# Underwater_vehicle-V2_0.net
KiCad netlist of a schematic drawn in Altium Designer
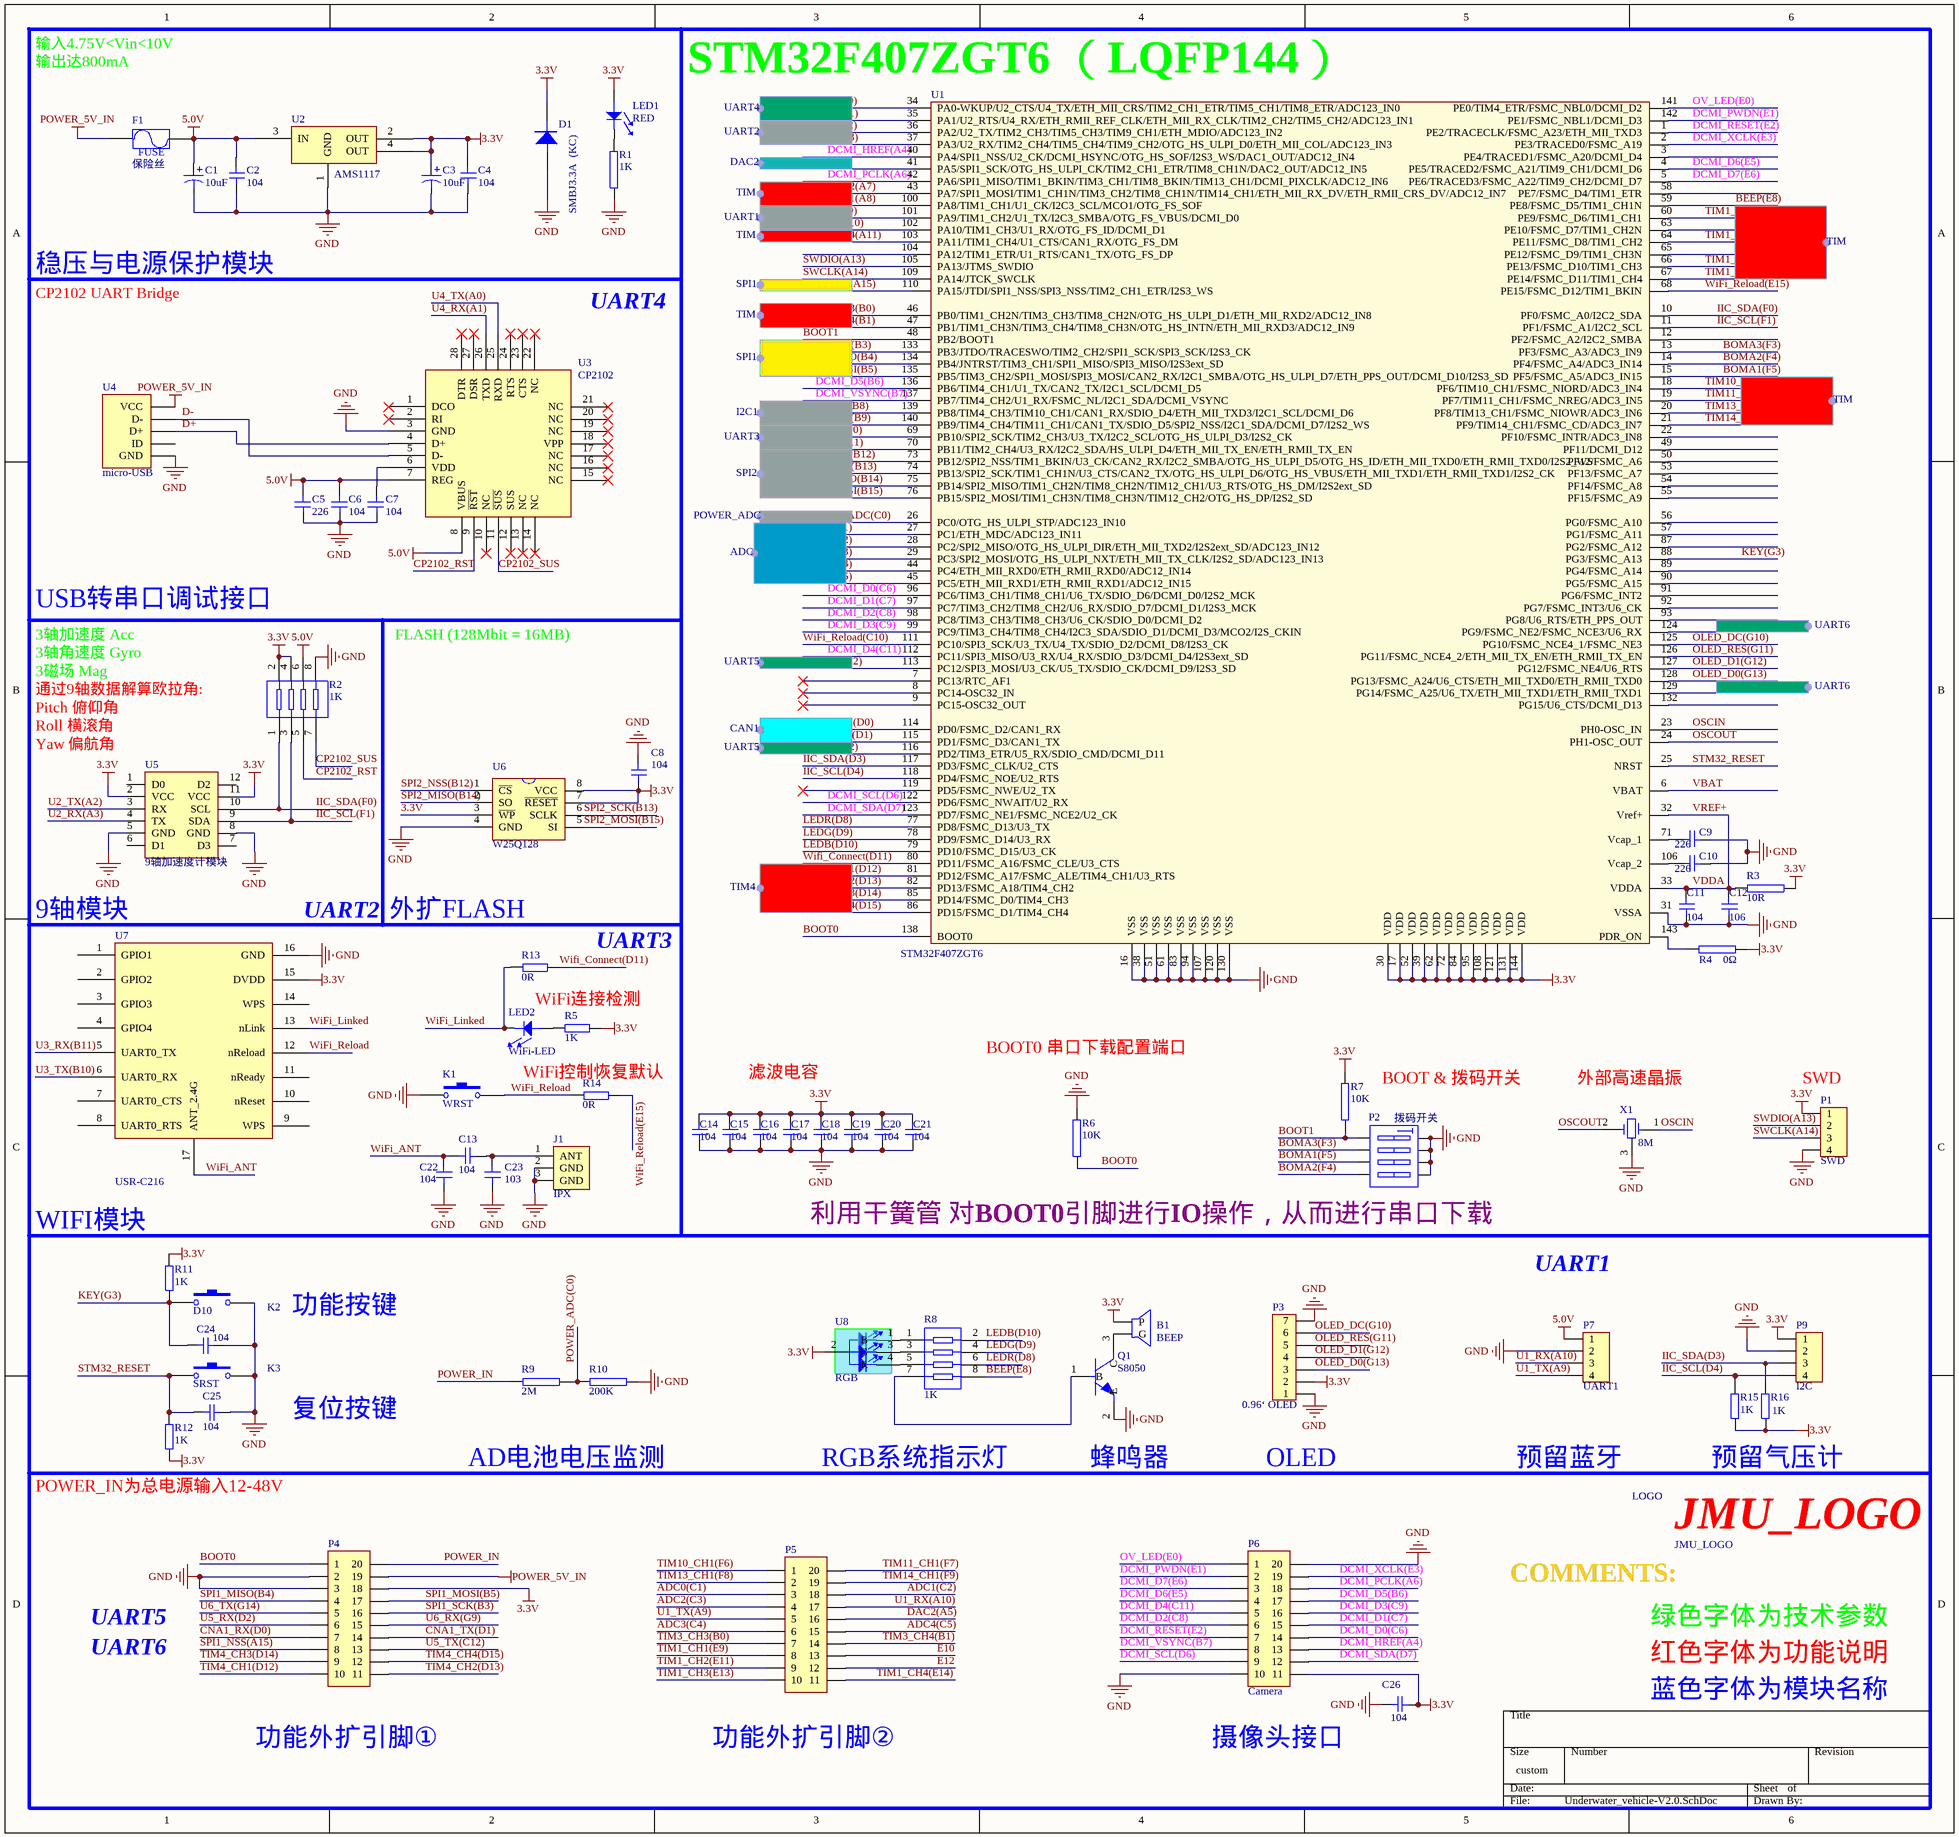
[diagram p0: Underwater_vehicle-V2.0.SchDoc]

(export (version "E")
  (design (tool "Eeschema 10.0.6"))
  (components
    (comp (ref "B1") (value "BEEP") (footprint "BUZZER") (libsource (lib "EXPLORER") (part "BEEP")))
    (comp (ref "C1")
      (value "10uF")
      (footprint "TAJ-A")
      (description "极性贴片电容")
      (libsource (lib "集大电协1.1.0") (part "Pol Cap"))
    )
    (comp (ref "C2")
      (value "104")
      (footprint "0805C")
      (description "无极贴片电容")
      (libsource (lib "集大电协1.1.0") (part "Cap1"))
    )
    (comp (ref "C3")
      (value "10uF")
      (footprint "TAJ-A")
      (description "极性贴片电容")
      (libsource (lib "集大电协1.1.0") (part "Pol Cap"))
    )
    (comp (ref "C4")
      (value "104")
      (footprint "0805C")
      (description "无极贴片电容")
      (libsource (lib "集大电协1.1.0") (part "Cap1"))
    )
    (comp (ref "C5")
      (value "226")
      (footprint "0805C")
      (description "无极贴片电容")
      (libsource (lib "集大电协1.1.0") (part "Cap1"))
    )
    (comp (ref "C6")
      (value "104")
      (footprint "0805C")
      (description "无极贴片电容")
      (libsource (lib "集大电协1.1.0") (part "Cap1"))
    )
    (comp (ref "C7")
      (value "104")
      (footprint "0805C")
      (description "无极贴片电容")
      (libsource (lib "集大电协1.1.0") (part "Cap1"))
    )
    (comp (ref "C8")
      (value "104")
      (footprint "0805C")
      (description "无极贴片电容")
      (libsource (lib "集大电协1.1.0") (part "Cap1"))
    )
    (comp (ref "C9") (value "226") (footprint "0805C") (libsource (lib "窝牛器件封装") (part "C1")))
    (comp (ref "C10") (value "226") (footprint "0805C") (libsource (lib "窝牛器件封装") (part "C1")))
    (comp (ref "C11") (value "104") (footprint "0805C") (libsource (lib "窝牛器件封装") (part "C1")))
    (comp (ref "C12") (value "106") (footprint "0805C") (libsource (lib "窝牛器件封装") (part "C1")))
    (comp (ref "C13")
      (value "104")
      (footprint "0805C")
      (description "无极贴片电容")
      (libsource (lib "集大电协1.1.2") (part "Cap1"))
    )
    (comp (ref "C14") (value "104") (footprint "0805C") (libsource (lib "窝牛器件封装") (part "C1")))
    (comp (ref "C15") (value "104") (footprint "0805C") (libsource (lib "窝牛器件封装") (part "C1")))
    (comp (ref "C16") (value "104") (footprint "0805C") (libsource (lib "窝牛器件封装") (part "C1")))
    (comp (ref "C17") (value "104") (footprint "0805C") (libsource (lib "窝牛器件封装") (part "C1")))
    (comp (ref "C18") (value "104") (footprint "0805C") (libsource (lib "窝牛器件封装") (part "C1")))
    (comp (ref "C19") (value "104") (footprint "0805C") (libsource (lib "窝牛器件封装") (part "C1")))
    (comp (ref "C20") (value "104") (footprint "0805C") (libsource (lib "窝牛器件封装") (part "C1")))
    (comp (ref "C21") (value "104") (footprint "0805C") (libsource (lib "窝牛器件封装") (part "C1")))
    (comp (ref "C22")
      (value "104")
      (footprint "0805C")
      (description "无极贴片电容")
      (libsource (lib "集大电协1.1.2") (part "Cap1"))
    )
    (comp (ref "C23")
      (value "103")
      (footprint "0805C")
      (description "无极贴片电容")
      (libsource (lib "集大电协1.1.2") (part "Cap1"))
    )
    (comp (ref "C24") (value "104") (footprint "0805C") (libsource (lib "窝牛器件封装") (part "C1")))
    (comp (ref "C25") (value "104") (footprint "0805C") (libsource (lib "窝牛器件封装") (part "C1")))
    (comp (ref "C26")
      (value "104")
      (footprint "0805C")
      (description "无极贴片电容")
      (libsource (lib "集大电协1.1.5") (part "Cap1"))
    )
    (comp (ref "D1")
      (value "SMBJ3.3A  (KC)")
      (footprint "SMBJ")
      (description "二极管")
      (libsource (lib "集大电协1.1.0") (part "Diode"))
    )
    (comp (ref "F1") (value "保险丝") (footprint "1812") (libsource (lib "集大电协1.1.2") (part "Fuse")))
    (comp (ref "J1") (value "IPX") (footprint "IPX天线底座") (libsource (lib "集大电协1.1.2") (part "IPX天线座")))
    (comp (ref "K1")
      (value "WRST")
      (footprint "贴片按键")
      (description "轻触开关")
      (libsource (lib "集大电协1.1.2") (part "轻触按键"))
    )
    (comp (ref "K2") (value "D10") (footprint "贴片按键") (libsource (lib "窝牛器件封装") (part "Key(两脚贴片)")))
    (comp (ref "K3") (value "SRST") (footprint "贴片按键") (libsource (lib "窝牛器件封装") (part "Key(两脚贴片)")))
    (comp (ref "LED1")
      (value "RED")
      (footprint "0805LED(RED)")
      (description "发光二极管")
      (libsource (lib "集大电协1.1.2") (part "LED"))
    )
    (comp (ref "LED2")
      (value "WiFi-LED")
      (footprint "0805LED(GREEN)")
      (description "发光二极管")
      (libsource (lib "集大电协1.1.2") (part "LED"))
    )
    (comp (ref "LOGO")
      (value "JMU_LOGO")
      (footprint "JMU_LOGO(1.35cm)")
      (description "LOGO")
      (libsource (lib "集大电协1.1.5") (part "JMU_LOGO"))
    )
    (comp (ref "P1")
      (value "SWD")
      (footprint "Header 4")
      (description "排针")
      (libsource (lib "集大电协1.1.0") (part "Header 4"))
    )
    (comp (ref "P2")
      (value "拨码开关")
      (footprint "拨码开关(4位贴片)")
      (description "4位拨码开关")
      (libsource (lib "集大电协1.1.2") (part "拨码开关4"))
    )
    (comp (ref "P3")
      (value "0.96‘ OLED")
      (footprint "Header 7")
      (description "排针")
      (libsource (lib "集大电协1.1.5") (part "Header 7"))
    )
    (comp (ref "P4") (value "~") (footprint "Header 10X2") (libsource (lib "集大电协1.1.2") (part "Header 10X2")))
    (comp (ref "P5") (value "~") (footprint "Header 10X2") (libsource (lib "集大电协1.1.2") (part "Header 10X2")))
    (comp (ref "P6")
      (value "Camera")
      (footprint "Header 10X2")
      (libsource (lib "集大电协1.1.2") (part "Header 10X2"))
    )
    (comp (ref "P7")
      (value "UART1")
      (footprint "Header 4(排母)")
      (description "排针")
      (libsource (lib "集大电协1.1.5") (part "Header 4"))
    )
    (comp (ref "P9")
      (value "I2C")
      (footprint "Header 4(排母)")
      (description "排针")
      (libsource (lib "集大电协1.1.5") (part "Header 4"))
    )
    (comp (ref "Q1")
      (value "S8050")
      (footprint "SOT-23")
      (description "NPN三极管")
      (libsource (lib "集大电协1.1.2") (part "NPN"))
    )
    (comp (ref "R1") (value "1K") (footprint "0805R") (libsource (lib "窝牛器件封装") (part "R1")))
    (comp (ref "R2")
      (value "1K")
      (footprint "排阻(4位贴片)")
      (description "排阻")
      (libsource (lib "集大电协1.1.2") (part "Res-4"))
    )
    (comp (ref "R3") (value "10R") (footprint "0805R") (libsource (lib "窝牛器件封装") (part "R1")))
    (comp (ref "R4") (value "0Ω") (footprint "0805R") (libsource (lib "窝牛器件封装") (part "R1")))
    (comp (ref "R5")
      (value "1K")
      (footprint "0805R")
      (description "电阻")
      (libsource (lib "集大电协1.1.2") (part "Res"))
    )
    (comp (ref "R6") (value "10K") (footprint "0805R") (libsource (lib "窝牛器件封装") (part "R1")))
    (comp (ref "R7") (value "10K") (footprint "0805R") (libsource (lib "窝牛器件封装") (part "R1")))
    (comp (ref "R8")
      (value "1K")
      (footprint "排阻(4位贴片)")
      (description "排阻")
      (libsource (lib "集大电协1.1.2") (part "Res-4"))
    )
    (comp (ref "R9") (value "2M") (footprint "0805R") (libsource (lib "窝牛器件封装") (part "R1")))
    (comp (ref "R10") (value "200K") (footprint "0805R") (libsource (lib "窝牛器件封装") (part "R1")))
    (comp (ref "R11")
      (value "1K")
      (footprint "0805R")
      (description "电阻")
      (libsource (lib "集大电协1.1.5") (part "Res"))
    )
    (comp (ref "R12")
      (value "1K")
      (footprint "0805R")
      (description "电阻")
      (libsource (lib "集大电协1.1.5") (part "Res"))
    )
    (comp (ref "R13")
      (value "0R")
      (footprint "0805R")
      (description "电阻")
      (libsource (lib "集大电协1.1.5") (part "Res"))
    )
    (comp (ref "R14")
      (value "0R")
      (footprint "0805R")
      (description "电阻")
      (libsource (lib "集大电协1.1.5") (part "Res"))
    )
    (comp (ref "R15")
      (value "1K")
      (footprint "0805R")
      (description "电阻")
      (libsource (lib "集大电协1.2") (part "Res"))
    )
    (comp (ref "R16")
      (value "1K")
      (footprint "0805R")
      (description "电阻")
      (libsource (lib "集大电协1.2") (part "Res"))
    )
    (comp (ref "U1")
      (value "STM32F407ZGT6")
      (footprint "LQFP-144")
      (libsource (lib "窝牛器件封装") (part "STM32F407ZET6"))
    )
    (comp (ref "U2")
      (value "AMS1117")
      (footprint "SOT-223")
      (description "电源芯片")
      (libsource (lib "集大电协1.1.0") (part "AMS1117-3.3V/5.0V"))
    )
    (comp (ref "U3")
      (value "CP2102")
      (footprint "QFN-28")
      (description "USB转串口芯片")
      (libsource (lib "集大电协1.1.0") (part "CP2102"))
    )
    (comp (ref "U4")
      (value "micro-USB")
      (footprint "Micro-USB (兼容牛角)")
      (description "USB接口")
      (libsource (lib "集大电协1.1.2") (part "micro-USB"))
    )
    (comp (ref "U5") (value "9轴加速度计模块") (footprint "9轴加速度计") (libsource (lib "窝牛器件封装") (part "9轴加速度计")))
    (comp (ref "U6")
      (value "W25Q128")
      (footprint "SOW-8")
      (description "FLASH芯片")
      (libsource (lib "集大电协1.1.0") (part "W25Q128"))
    )
    (comp (ref "U7") (value "USR-C216") (footprint "USR-C216") (libsource (lib "集大电协1.2") (part "USR-C216")))
    (comp (ref "U8") (value "RGB") (footprint "RGB-3528") (libsource (lib "集大电协1.1.2") (part "RGB")))
    (comp (ref "X1") (value "8M") (footprint "三脚贴片8M晶振") (libsource (lib "集大电协1.1.2") (part "XTAL三脚贴片晶振")))
  )
  (nets
    (net (code "2") (name "/ADC0(C1)") (class "Default")
      (node (ref "P5") (pin "3") (pinfunction "3_3") (pintype "passive"))
      (node (ref "U1") (pin "27") (pinfunction "PC1/ETH_MDC/ADC123_IN11_27") (pintype "passive"))
    )
    (net (code "3") (name "/ADC1(C2)") (class "Default")
      (node (ref "P5") (pin "18") (pinfunction "18_18") (pintype "passive"))
      (node (ref "U1") (pin "28") (pinfunction "PC2/SPI2_MISO/OTG_HS_ULPI_DIR/ETH_MII_TXD2/I2S2ext_SD/ADC123_IN12_28") (pintype "passive"))
    )
    (net (code "4") (name "/ADC2(C3)") (class "Default")
      (node (ref "P5") (pin "4") (pinfunction "4_4") (pintype "passive"))
      (node (ref "U1") (pin "29") (pinfunction "PC3/SPI2_MOSI/OTG_HS_ULPI_NXT/ETH_MII_TX_CLK/I2S2_SD/ADC123_IN13_29") (pintype "passive"))
    )
    (net (code "5") (name "/ADC3(C4)") (class "Default")
      (node (ref "P5") (pin "6") (pinfunction "6_6") (pintype "passive"))
      (node (ref "U1") (pin "44") (pinfunction "PC4/ETH_MII_RXD0/ETH_RMII_RXD0/ADC12_IN14_44") (pintype "passive"))
    )
    (net (code "6") (name "/ADC4(C5)") (class "Default")
      (node (ref "P5") (pin "15") (pinfunction "15_15") (pintype "passive"))
      (node (ref "U1") (pin "45") (pinfunction "PC5/ETH_MII_RXD1/ETH_RMII_RXD1/ADC12_IN15_45") (pintype "passive"))
    )
    (net (code "7") (name "/BEEP(E8)") (class "Default")
      (node (ref "R8") (pin "8") (pinfunction "8_8") (pintype "passive"))
      (node (ref "U1") (pin "59") (pinfunction "PE8/FSMC_D5/TIM1_CH1N_59") (pintype "passive"))
    )
    (net (code "8") (name "/BOMA1(F5)") (class "Default")
      (node (ref "P2") (pin "3") (pinfunction "A3_3") (pintype "passive"))
      (node (ref "U1") (pin "15") (pinfunction "PF5/FSMC_A5/ADC3_IN15_15") (pintype "passive"))
    )
    (net (code "9") (name "/BOMA2(F4)") (class "Default")
      (node (ref "P2") (pin "4") (pinfunction "A4_4") (pintype "passive"))
      (node (ref "U1") (pin "14") (pinfunction "PF4/FSMC_A4/ADC3_IN14_14") (pintype "passive"))
    )
    (net (code "10") (name "/BOMA3(F3)") (class "Default")
      (node (ref "P2") (pin "2") (pinfunction "A2_2") (pintype "passive"))
      (node (ref "U1") (pin "13") (pinfunction "PF3/FSMC_A3/ADC3_IN9_13") (pintype "passive"))
    )
    (net (code "11") (name "/BOOT0") (class "Default")
      (node (ref "P4") (pin "1") (pinfunction "1_1") (pintype "passive"))
      (node (ref "R6") (pin "1") (pinfunction "1_1") (pintype "passive"))
      (node (ref "U1") (pin "138") (pinfunction "BOOT0_138") (pintype "passive"))
    )
    (net (code "12") (name "/BOOT1") (class "Default")
      (node (ref "P2") (pin "1") (pinfunction "A1_1") (pintype "passive"))
      (node (ref "R7") (pin "1") (pinfunction "1_1") (pintype "passive"))
      (node (ref "U1") (pin "48") (pinfunction "PB2/BOOT1_48") (pintype "passive"))
    )
    (net (code "13") (name "/CNA1_RX(D0)") (class "Default")
      (node (ref "P4") (pin "7") (pinfunction "7_7") (pintype "passive"))
      (node (ref "U1") (pin "114") (pinfunction "PD0/FSMC_D2/CAN1_RX_114") (pintype "passive"))
    )
    (net (code "14") (name "/CNA1_TX(D1)") (class "Default")
      (node (ref "P4") (pin "14") (pinfunction "14_14") (pintype "passive"))
      (node (ref "U1") (pin "115") (pinfunction "PD1/FSMC_D3/CAN1_TX_115") (pintype "passive"))
    )
    (net (code "15") (name "/CP2102_RST") (class "Default")
      (node (ref "R2") (pin "5") (pinfunction "5_5") (pintype "passive"))
      (node (ref "U3") (pin "9") (pinfunction "~{RST}_9") (pintype "passive"))
    )
    (net (code "16") (name "/CP2102_SUS") (class "Default")
      (node (ref "R2") (pin "7") (pinfunction "7_7") (pintype "passive"))
      (node (ref "U3") (pin "11") (pinfunction "~{SUS}_11") (pintype "passive"))
    )
    (net (code "17") (name "/D+") (class "Default")
      (node (ref "U3") (pin "4") (pinfunction "D+_4") (pintype "passive"))
      (node (ref "U4") (pin "3") (pinfunction "D+_3") (pintype "power_in"))
    )
    (net (code "18") (name "/D-") (class "Default")
      (node (ref "U3") (pin "5") (pinfunction "D-_5") (pintype "passive"))
      (node (ref "U4") (pin "2") (pinfunction "D-_2") (pintype "power_in"))
    )
    (net (code "19") (name "/DAC2(A5)") (class "Default")
      (node (ref "P5") (pin "16") (pinfunction "16_16") (pintype "passive"))
      (node (ref "U1") (pin "41") (pinfunction "PA5/SPI1_SCK/OTG_HS_ULPI_CK/TIM2_CH1_ETR/TIM8_CH1N/DAC2_OUT/ADC12_IN5_41") (pintype "passive"))
    )
    (net (code "20") (name "/DCMI_D0(C6)") (class "Default")
      (node (ref "P6") (pin "14") (pinfunction "14_14") (pintype "passive"))
      (node (ref "U1") (pin "96") (pinfunction "PC6/TIM3_CH1/TIM8_CH1/U6_TX/SDIO_D6/DCMI_D0/I2S2_MCK_96") (pintype "passive"))
    )
    (net (code "21") (name "/DCMI_D1(C7)") (class "Default")
      (node (ref "P6") (pin "15") (pinfunction "15_15") (pintype "passive"))
      (node (ref "U1") (pin "97") (pinfunction "PC7/TIM3_CH2/TIM8_CH2/U6_RX/SDIO_D7/DCMI_D1/I2S3_MCK_97") (pintype "passive"))
    )
    (net (code "22") (name "/DCMI_D2(C8)") (class "Default")
      (node (ref "P6") (pin "6") (pinfunction "6_6") (pintype "passive"))
      (node (ref "U1") (pin "98") (pinfunction "PC8/TIM3_CH3/TIM8_CH3/U6_CK/SDIO_D0/DCMI_D2_98") (pintype "passive"))
    )
    (net (code "23") (name "/DCMI_D3(C9)") (class "Default")
      (node (ref "P6") (pin "16") (pinfunction "16_16") (pintype "passive"))
      (node (ref "U1") (pin "99") (pinfunction "PC9/TIM3_CH4/TIM8_CH4/I2C3_SDA/SDIO_D1/DCMI_D3/MCO2/I2S_CKIN_99") (pintype "passive"))
    )
    (net (code "24") (name "/DCMI_D4(C11)") (class "Default")
      (node (ref "P6") (pin "5") (pinfunction "5_5") (pintype "passive"))
      (node (ref "U1") (pin "112") (pinfunction "PC11/SPI3_MISO/U3_RX/U4_RX/SDIO_D3/DCMI_D4/I2S3ext_SD_112") (pintype "passive"))
    )
    (net (code "25") (name "/DCMI_D5(B6)") (class "Default")
      (node (ref "P6") (pin "17") (pinfunction "17_17") (pintype "passive"))
      (node (ref "U1") (pin "136") (pinfunction "PB6/TIM4_CH1/U1_TX/CAN2_TX/I2C1_SCL/DCMI_D5_136") (pintype "passive"))
    )
    (net (code "26") (name "/DCMI_D6(E5)") (class "Default")
      (node (ref "P6") (pin "4") (pinfunction "4_4") (pintype "passive"))
      (node (ref "U1") (pin "4") (pinfunction "PE5/TRACED2/FSMC_A21/TIM9_CH1/DCMI_D6_4") (pintype "passive"))
    )
    (net (code "27") (name "/DCMI_D7(E6)") (class "Default")
      (node (ref "P6") (pin "3") (pinfunction "3_3") (pintype "passive"))
      (node (ref "U1") (pin "5") (pinfunction "PE6/TRACED3/FSMC_A22/TIM9_CH2/DCMI_D7_5") (pintype "passive"))
    )
    (net (code "28") (name "/DCMI_HREF(A4)") (class "Default")
      (node (ref "P6") (pin "13") (pinfunction "13_13") (pintype "passive"))
      (node (ref "U1") (pin "40") (pinfunction "PA4/SPI1_NSS/U2_CK/DCMI_HSYNC/OTG_HS_SOF/I2S3_WS/DAC1_OUT/ADC12_IN4_40") (pintype "passive"))
    )
    (net (code "29") (name "/DCMI_PCLK(A6)") (class "Default")
      (node (ref "P6") (pin "18") (pinfunction "18_18") (pintype "passive"))
      (node (ref "U1") (pin "42") (pinfunction "PA6/SPI1_MISO/TIM1_BKIN/TIM3_CH1/TIM8_BKIN/TIM13_CH1/DCMI_PIXCLK/ADC12_IN6_42") (pintype "passive"))
    )
    (net (code "30") (name "/DCMI_PWDN(E1)") (class "Default")
      (node (ref "P6") (pin "2") (pinfunction "2_2") (pintype "passive"))
      (node (ref "U1") (pin "142") (pinfunction "PE1/FSMC_NBL1/DCMI_D3_142") (pintype "passive"))
    )
    (net (code "31") (name "/DCMI_RESET(E2)") (class "Default")
      (node (ref "P6") (pin "7") (pinfunction "7_7") (pintype "passive"))
      (node (ref "U1") (pin "1") (pinfunction "PE2/TRACECLK/FSMC_A23/ETH_MII_TXD3_1") (pintype "passive"))
    )
    (net (code "32") (name "/DCMI_SCL(D6)") (class "Default")
      (node (ref "P6") (pin "9") (pinfunction "9_9") (pintype "passive"))
      (node (ref "U1") (pin "122") (pinfunction "PD6/FSMC_NWAIT/U2_RX_122") (pintype "passive"))
    )
    (net (code "33") (name "/DCMI_SDA(D7)") (class "Default")
      (node (ref "P6") (pin "12") (pinfunction "12_12") (pintype "passive"))
      (node (ref "U1") (pin "123") (pinfunction "PD7/FSMC_NE1/FSMC_NCE2/U2_CK_123") (pintype "passive"))
    )
    (net (code "34") (name "/DCMI_VSYNC(B7)") (class "Default")
      (node (ref "P6") (pin "8") (pinfunction "8_8") (pintype "passive"))
      (node (ref "U1") (pin "137") (pinfunction "PB7/TIM4_CH2/U1_RX/FSMC_NL/I2C1_SDA/DCMI_VSYNC_137") (pintype "passive"))
    )
    (net (code "35") (name "/DCMI_XCLK(E3)") (class "Default")
      (node (ref "P6") (pin "19") (pinfunction "19_19") (pintype "passive"))
      (node (ref "U1") (pin "2") (pinfunction "PE3/TRACED0/FSMC_A19_2") (pintype "passive"))
    )
    (net (code "36") (name "/E10") (class "Default")
      (node (ref "P5") (pin "13") (pinfunction "13_13") (pintype "passive"))
      (node (ref "U1") (pin "63") (pinfunction "PE10/FSMC_D7/TIM1_CH2N_63") (pintype "passive"))
    )
    (net (code "37") (name "/E12") (class "Default")
      (node (ref "P5") (pin "12") (pinfunction "12_12") (pintype "passive"))
      (node (ref "U1") (pin "65") (pinfunction "PE12/FSMC_D9/TIM1_CH3N_65") (pintype "passive"))
    )
    (net (code "38") (name "/IIC1_SCL(B8)") (class "Default")
      (node (ref "U1") (pin "139") (pinfunction "PB8/TIM4_CH3/TIM10_CH1/CAN1_RX/SDIO_D4/ETH_MII_TXD3/I2C1_SCL/DCMI_D6_139") (pintype "passive"))
    )
    (net (code "39") (name "/IIC1_SDA(B9)") (class "Default")
      (node (ref "U1") (pin "140") (pinfunction "PB9/TIM4_CH4/TIM11_CH1/CAN1_TX/SDIO_D5/SPI2_NSS/I2C1_SDA/DCMI_D7/I2S2_WS_140") (pintype "passive"))
    )
    (net (code "40") (name "/IIC_SCL(D4)") (class "Default")
      (node (ref "P9") (pin "4") (pinfunction "4_4") (pintype "passive"))
      (node (ref "R15") (pin "2") (pinfunction "2_2") (pintype "passive"))
      (node (ref "U1") (pin "118") (pinfunction "PD4/FSMC_NOE/U2_RTS_118") (pintype "passive"))
    )
    (net (code "41") (name "/IIC_SCL(F1)") (class "Default")
      (node (ref "R2") (pin "3") (pinfunction "3_3") (pintype "passive"))
      (node (ref "U1") (pin "11") (pinfunction "PF1/FSMC_A1/I2C2_SCL_11") (pintype "passive"))
      (node (ref "U5") (pin "9") (pinfunction "SDA_9") (pintype "passive"))
    )
    (net (code "42") (name "/IIC_SDA(D3)") (class "Default")
      (node (ref "P9") (pin "3") (pinfunction "3_3") (pintype "passive"))
      (node (ref "R16") (pin "2") (pinfunction "2_2") (pintype "passive"))
      (node (ref "U1") (pin "117") (pinfunction "PD3/FSMC_CLK/U2_CTS_117") (pintype "passive"))
    )
    (net (code "43") (name "/IIC_SDA(F0)") (class "Default")
      (node (ref "R2") (pin "1") (pinfunction "1_1") (pintype "passive"))
      (node (ref "U1") (pin "10") (pinfunction "PF0/FSMC_A0/I2C2_SDA_10") (pintype "passive"))
      (node (ref "U5") (pin "10") (pinfunction "SCL_10") (pintype "passive"))
    )
    (net (code "44") (name "/KEY(G3)") (class "Default")
      (node (ref "C24") (pin "1") (pinfunction "1_1") (pintype "passive"))
      (node (ref "K2") (pin "1") (pinfunction "1_1") (pintype "passive"))
      (node (ref "R11") (pin "1") (pinfunction "1_1") (pintype "passive"))
      (node (ref "U1") (pin "88") (pinfunction "PG3/FSMC_A13_88") (pintype "passive"))
    )
    (net (code "45") (name "/LEDB(D10)") (class "Default")
      (node (ref "R8") (pin "2") (pinfunction "2_2") (pintype "passive"))
      (node (ref "U1") (pin "79") (pinfunction "PD10/FSMC_D15/U3_CK_79") (pintype "passive"))
    )
    (net (code "46") (name "/LEDG(D9)") (class "Default")
      (node (ref "R8") (pin "4") (pinfunction "4_4") (pintype "passive"))
      (node (ref "U1") (pin "78") (pinfunction "PD9/FSMC_D14/U3_RX_78") (pintype "passive"))
    )
    (net (code "47") (name "/LEDR(D8)") (class "Default")
      (node (ref "R8") (pin "6") (pinfunction "6_6") (pintype "passive"))
      (node (ref "U1") (pin "77") (pinfunction "PD8/FSMC_D13/U3_TX_77") (pintype "passive"))
    )
    (net (code "48") (name "/OLED_D0(G13)") (class "Default")
      (node (ref "P3") (pin "3") (pinfunction "3_3") (pintype "passive"))
      (node (ref "U1") (pin "128") (pinfunction "PG13/FSMC_A24/U6_CTS/ETH_MII_TXD0/ETH_RMII_TXD0_128") (pintype "passive"))
    )
    (net (code "49") (name "/OLED_D1(G12)") (class "Default")
      (node (ref "P3") (pin "4") (pinfunction "4_4") (pintype "passive"))
      (node (ref "U1") (pin "127") (pinfunction "PG12/FSMC_NE4/U6_RTS_127") (pintype "passive"))
    )
    (net (code "50") (name "/OLED_DC(G10)") (class "Default")
      (node (ref "P3") (pin "6") (pinfunction "6_6") (pintype "passive"))
      (node (ref "U1") (pin "125") (pinfunction "PG10/FSMC_NCE4_1/FSMC_NE3_125") (pintype "passive"))
    )
    (net (code "51") (name "/OLED_RES(G11)") (class "Default")
      (node (ref "P3") (pin "5") (pinfunction "5_5") (pintype "passive"))
      (node (ref "U1") (pin "126") (pinfunction "PG11/FSMC_NCE4_2/ETH_MII_TX_EN/ETH_RMII_TX_EN_126") (pintype "passive"))
    )
    (net (code "52") (name "/OSCIN") (class "Default")
      (node (ref "U1") (pin "23") (pinfunction "PH0-OSC_IN_23") (pintype "passive"))
      (node (ref "X1") (pin "1") (pinfunction "1_1") (pintype "passive"))
    )
    (net (code "53") (name "/OSCOUT") (class "Default")
      (node (ref "U1") (pin "24") (pinfunction "PH1-OSC_OUT_24") (pintype "passive"))
      (node (ref "X1") (pin "2") (pinfunction "2_2") (pintype "passive"))
    )
    (net (code "54") (name "/OV_LED(E0)") (class "Default")
      (node (ref "P6") (pin "1") (pinfunction "1_1") (pintype "passive"))
      (node (ref "U1") (pin "141") (pinfunction "PE0/TIM4_ETR/FSMC_NBL0/DCMI_D2_141") (pintype "passive"))
    )
    (net (code "55") (name "/POWER_ADC(C0)") (class "Default")
      (node (ref "R10") (pin "1") (pinfunction "1_1") (pintype "passive"))
      (node (ref "R9") (pin "2") (pinfunction "2_2") (pintype "passive"))
      (node (ref "U1") (pin "26") (pinfunction "PC0/OTG_HS_ULPI_STP/ADC123_IN10_26") (pintype "passive"))
    )
    (net (code "56") (name "/POWER_IN") (class "Default")
      (node (ref "P4") (pin "20") (pinfunction "20_20") (pintype "passive"))
      (node (ref "R9") (pin "1") (pinfunction "1_1") (pintype "passive"))
    )
    (net (code "57") (name "/SPI1_MISO(B4)") (class "Default")
      (node (ref "P4") (pin "4") (pinfunction "4_4") (pintype "passive"))
      (node (ref "U1") (pin "134") (pinfunction "PB4/JNTRST/TIM3_CH1/SPI1_MISO/SPI3_MISO/I2S3ext_SD_134") (pintype "passive"))
    )
    (net (code "58") (name "/SPI1_MOSI(B5)") (class "Default")
      (node (ref "P4") (pin "17") (pinfunction "17_17") (pintype "passive"))
      (node (ref "U1") (pin "135") (pinfunction "PB5/TIM3_CH2/SPI1_MOSI/SPI3_MOSI/CAN2_RX/I2C1_SMBA/OTG_HS_ULPI_D7/ETH_PPS_OUT/DCMI_D10/I2S3_SD_135") (pintype "passive"))
    )
    (net (code "59") (name "/SPI1_NSS(A15)") (class "Default")
      (node (ref "P4") (pin "8") (pinfunction "8_8") (pintype "passive"))
      (node (ref "U1") (pin "110") (pinfunction "PA15/JTDI/SPI1_NSS/SPI3_NSS/TIM2_CH1_ETR/I2S3_WS_110") (pintype "passive"))
    )
    (net (code "60") (name "/SPI1_SCK(B3)") (class "Default")
      (node (ref "P4") (pin "16") (pinfunction "16_16") (pintype "passive"))
      (node (ref "U1") (pin "133") (pinfunction "PB3/JTDO/TRACESWO/TIM2_CH2/SPI1_SCK/SPI3_SCK/I2S3_CK_133") (pintype "passive"))
    )
    (net (code "61") (name "/SPI2_MISO(B14)") (class "Default")
      (node (ref "U1") (pin "75") (pinfunction "PB14/SPI2_MISO/TIM1_CH2N/TIM8_CH2N/TIM12_CH1/U3_RTS/OTG_HS_DM/I2S2ext_SD_75") (pintype "passive"))
      (node (ref "U6") (pin "2") (pinfunction "SO_2") (pintype "passive"))
    )
    (net (code "62") (name "/SPI2_MOSI(B15)") (class "Default")
      (node (ref "U1") (pin "76") (pinfunction "PB15/SPI2_MOSI/TIM1_CH3N/TIM8_CH3N/TIM12_CH2/OTG_HS_DP/I2S2_SD_76") (pintype "passive"))
      (node (ref "U6") (pin "5") (pinfunction "SI_5") (pintype "passive"))
    )
    (net (code "63") (name "/SPI2_NSS(B12)") (class "Default")
      (node (ref "U1") (pin "73") (pinfunction "PB12/SPI2_NSS/TIM1_BKIN/U3_CK/CAN2_RX/I2C2_SMBA/OTG_HS_ULPI_D5/OTG_HS_ID/ETH_MII_TXD0/ETH_RMII_TXD0/I2S2_WS_73") (pintype "passive"))
      (node (ref "U6") (pin "1") (pinfunction "~{CS}_1") (pintype "passive"))
    )
    (net (code "64") (name "/SPI2_SCK(B13)") (class "Default")
      (node (ref "U1") (pin "74") (pinfunction "PB13/SPI2_SCK/TIM1_CH1N/U3_CTS/CAN2_TX/OTG_HS_ULPI_D6/OTG_HS_VBUS/ETH_MII_TXD1/ETH_RMII_TXD1/I2S2_CK_74") (pintype "passive"))
      (node (ref "U6") (pin "6") (pinfunction "SCLK_6") (pintype "passive"))
    )
    (net (code "65") (name "/STM32_RESET") (class "Default")
      (node (ref "C25") (pin "1") (pinfunction "1_1") (pintype "passive"))
      (node (ref "K3") (pin "1") (pinfunction "1_1") (pintype "passive"))
      (node (ref "R12") (pin "2") (pinfunction "2_2") (pintype "passive"))
      (node (ref "U1") (pin "25") (pinfunction "NRST_25") (pintype "passive"))
    )
    (net (code "66") (name "/SWCLK(A14)") (class "Default")
      (node (ref "P1") (pin "3") (pinfunction "3_3") (pintype "passive"))
      (node (ref "U1") (pin "109") (pinfunction "PA14/JTCK_SWCLK_109") (pintype "passive"))
    )
    (net (code "67") (name "/SWDIO(A13)") (class "Default")
      (node (ref "P1") (pin "2") (pinfunction "2_2") (pintype "passive"))
      (node (ref "U1") (pin "105") (pinfunction "PA13/JTMS_SWDIO_105") (pintype "passive"))
    )
    (net (code "68") (name "/TIM1_CH1(A8)") (class "Default")
      (node (ref "U1") (pin "100") (pinfunction "PA8/TIM1_CH1/U1_CK/I2C3_SCL/MCO1/OTG_FS_SOF_100") (pintype "passive"))
    )
    (net (code "69") (name "/TIM1_CH1(E9)") (class "Default")
      (node (ref "P5") (pin "8") (pinfunction "8_8") (pintype "passive"))
      (node (ref "U1") (pin "60") (pinfunction "PE9/FSMC_D6/TIM1_CH1_60") (pintype "passive"))
    )
    (net (code "70") (name "/TIM1_CH2(E11)") (class "Default")
      (node (ref "P5") (pin "9") (pinfunction "9_9") (pintype "passive"))
      (node (ref "U1") (pin "64") (pinfunction "PE11/FSMC_D8/TIM1_CH2_64") (pintype "passive"))
    )
    (net (code "71") (name "/TIM1_CH3(E13)") (class "Default")
      (node (ref "P5") (pin "10") (pinfunction "10_10") (pintype "passive"))
      (node (ref "U1") (pin "66") (pinfunction "PE13/FSMC_D10/TIM1_CH3_66") (pintype "passive"))
    )
    (net (code "72") (name "/TIM1_CH4(A11)") (class "Default")
      (node (ref "U1") (pin "103") (pinfunction "PA11/TIM1_CH4/U1_CTS/CAN1_RX/OTG_FS_DM_103") (pintype "passive"))
    )
    (net (code "73") (name "/TIM1_CH4(E14)") (class "Default")
      (node (ref "P5") (pin "11") (pinfunction "11_11") (pintype "passive"))
      (node (ref "U1") (pin "67") (pinfunction "PE14/FSMC_D11/TIM1_CH4_67") (pintype "passive"))
    )
    (net (code "74") (name "/TIM3_CH2(A7)") (class "Default")
      (node (ref "U1") (pin "43") (pinfunction "PA7/SPI1_MOSI/TIM1_CH1N/TIM3_CH2/TIM8_CH1N/TIM14_CH1/ETH_MII_RX_DV/ETH_RMII_CRS_DV/ADC12_IN7_43") (pintype "passive"))
    )
    (net (code "75") (name "/TIM3_CH3(B0)") (class "Default")
      (node (ref "P5") (pin "7") (pinfunction "7_7") (pintype "passive"))
      (node (ref "U1") (pin "46") (pinfunction "PB0/TIM1_CH2N/TIM3_CH3/TIM8_CH2N/OTG_HS_ULPI_D1/ETH_MII_RXD2/ADC12_IN8_46") (pintype "passive"))
    )
    (net (code "76") (name "/TIM3_CH4(B1)") (class "Default")
      (node (ref "P5") (pin "14") (pinfunction "14_14") (pintype "passive"))
      (node (ref "U1") (pin "47") (pinfunction "PB1/TIM1_CH3N/TIM3_CH4/TIM8_CH3N/OTG_HS_INTN/ETH_MII_RXD3/ADC12_IN9_47") (pintype "passive"))
    )
    (net (code "77") (name "/TIM4_CH1(D12)") (class "Default")
      (node (ref "P4") (pin "10") (pinfunction "10_10") (pintype "passive"))
      (node (ref "U1") (pin "81") (pinfunction "PD12/FSMC_A17/FSMC_ALE/TIM4_CH1/U3_RTS_81") (pintype "passive"))
    )
    (net (code "78") (name "/TIM4_CH2(D13)") (class "Default")
      (node (ref "P4") (pin "11") (pinfunction "11_11") (pintype "passive"))
      (node (ref "U1") (pin "82") (pinfunction "PD13/FSMC_A18/TIM4_CH2_82") (pintype "passive"))
    )
    (net (code "79") (name "/TIM4_CH3(D14)") (class "Default")
      (node (ref "P4") (pin "9") (pinfunction "9_9") (pintype "passive"))
      (node (ref "U1") (pin "85") (pinfunction "PD14/FSMC_D0/TIM4_CH3_85") (pintype "passive"))
    )
    (net (code "80") (name "/TIM4_CH4(D15)") (class "Default")
      (node (ref "P4") (pin "12") (pinfunction "12_12") (pintype "passive"))
      (node (ref "U1") (pin "86") (pinfunction "PD15/FSMC_D1/TIM4_CH4_86") (pintype "passive"))
    )
    (net (code "81") (name "/TIM10_CH1(F6)") (class "Default")
      (node (ref "P5") (pin "1") (pinfunction "1_1") (pintype "passive"))
      (node (ref "U1") (pin "18") (pinfunction "PF6/TIM10_CH1/FSMC_NIORD/ADC3_IN4_18") (pintype "passive"))
    )
    (net (code "82") (name "/TIM11_CH1(F7)") (class "Default")
      (node (ref "P5") (pin "20") (pinfunction "20_20") (pintype "passive"))
      (node (ref "U1") (pin "19") (pinfunction "PF7/TIM11_CH1/FSMC_NREG/ADC3_IN5_19") (pintype "passive"))
    )
    (net (code "83") (name "/TIM13_CH1(F8)") (class "Default")
      (node (ref "P5") (pin "2") (pinfunction "2_2") (pintype "passive"))
      (node (ref "U1") (pin "20") (pinfunction "PF8/TIM13_CH1/FSMC_NIOWR/ADC3_IN6_20") (pintype "passive"))
    )
    (net (code "84") (name "/TIM14_CH1(F9)") (class "Default")
      (node (ref "P5") (pin "19") (pinfunction "19_19") (pintype "passive"))
      (node (ref "U1") (pin "21") (pinfunction "PF9/TIM14_CH1/FSMC_CD/ADC3_IN7_21") (pintype "passive"))
    )
    (net (code "85") (name "/U1_RX(A10)") (class "Default")
      (node (ref "P5") (pin "17") (pinfunction "17_17") (pintype "passive"))
      (node (ref "P7") (pin "3") (pinfunction "3_3") (pintype "passive"))
      (node (ref "U1") (pin "102") (pinfunction "PA10/TIM1_CH3/U1_RX/OTG_FS_ID/DCMI_D1_102") (pintype "passive"))
    )
    (net (code "86") (name "/U1_TX(A9)") (class "Default")
      (node (ref "P5") (pin "5") (pinfunction "5_5") (pintype "passive"))
      (node (ref "P7") (pin "4") (pinfunction "4_4") (pintype "passive"))
      (node (ref "U1") (pin "101") (pinfunction "PA9/TIM1_CH2/U1_TX/I2C3_SMBA/OTG_FS_VBUS/DCMI_D0_101") (pintype "passive"))
    )
    (net (code "87") (name "/U2_RX(A3)") (class "Default")
      (node (ref "U1") (pin "37") (pinfunction "PA3/U2_RX/TIM2_CH4/TIM5_CH4/TIM9_CH2/OTG_HS_ULPI_D0/ETH_MII_COL/ADC123_IN3_37") (pintype "passive"))
      (node (ref "U5") (pin "4") (pinfunction "TX_4") (pintype "passive"))
    )
    (net (code "88") (name "/U2_TX(A2)") (class "Default")
      (node (ref "U1") (pin "36") (pinfunction "PA2/U2_TX/TIM2_CH3/TIM5_CH3/TIM9_CH1/ETH_MDIO/ADC123_IN2_36") (pintype "passive"))
      (node (ref "U5") (pin "3") (pinfunction "RX_3") (pintype "passive"))
    )
    (net (code "89") (name "/U3_RX(B11)") (class "Default")
      (node (ref "U1") (pin "70") (pinfunction "PB11/TIM2_CH4/U3_RX/I2C2_SDA/HS_ULPI_D4/ETH_MII_TX_EN/ETH_RMII_TX_EN_70") (pintype "passive"))
      (node (ref "U7") (pin "5") (pinfunction "UART0_TX_5") (pintype "passive"))
    )
    (net (code "90") (name "/U3_TX(B10)") (class "Default")
      (node (ref "U1") (pin "69") (pinfunction "PB10/SPI2_SCK/TIM2_CH3/U3_TX/I2C2_SCL/OTG_HS_ULPI_D3/I2S2_CK_69") (pintype "passive"))
      (node (ref "U7") (pin "6") (pinfunction "UART0_RX_6") (pintype "passive"))
    )
    (net (code "91") (name "/U4_RX(A1)") (class "Default")
      (node (ref "U1") (pin "35") (pinfunction "PA1/U2_RTS/U4_RX/ETH_RMII_REF_CLK/ETH_MII_RX_CLK/TIM2_CH2/TIM5_CH2/ADC123_IN1_35") (pintype "passive"))
      (node (ref "U3") (pin "26") (pinfunction "TXD_26") (pintype "passive"))
    )
    (net (code "92") (name "/U4_TX(A0)") (class "Default")
      (node (ref "U1") (pin "34") (pinfunction "PA0-WKUP/U2_CTS/U4_TX/ETH_MII_CRS/TIM2_CH1_ETR/TIM5_CH1/TIM8_ETR/ADC123_IN0_34") (pintype "passive"))
      (node (ref "U3") (pin "25") (pinfunction "RXD_25") (pintype "passive"))
    )
    (net (code "93") (name "/U5_RX(D2)") (class "Default")
      (node (ref "P4") (pin "6") (pinfunction "6_6") (pintype "passive"))
      (node (ref "U1") (pin "116") (pinfunction "PD2/TIM3_ETR/U5_RX/SDIO_CMD/DCMI_D11_116") (pintype "passive"))
    )
    (net (code "94") (name "/U5_TX(C12)") (class "Default")
      (node (ref "P4") (pin "13") (pinfunction "13_13") (pintype "passive"))
      (node (ref "U1") (pin "113") (pinfunction "PC12/SPI3_MOSI/U3_CK/U5_TX/SDIO_CK/DCMI_D9/I2S3_SD_113") (pintype "passive"))
    )
    (net (code "95") (name "/U6_RX(G9)") (class "Default")
      (node (ref "P4") (pin "15") (pinfunction "15_15") (pintype "passive"))
      (node (ref "U1") (pin "124") (pinfunction "PG9/FSMC_NE2/FSMC_NCE3/U6_RX_124") (pintype "passive"))
    )
    (net (code "96") (name "/U6_TX(G14)") (class "Default")
      (node (ref "P4") (pin "5") (pinfunction "5_5") (pintype "passive"))
      (node (ref "U1") (pin "129") (pinfunction "PG14/FSMC_A25/U6_TX/ETH_MII_TXD1/ETH_RMII_TXD1_129") (pintype "passive"))
    )
    (net (code "97") (name "/VBAT") (class "Default")
      (node (ref "U1") (pin "6") (pinfunction "VBAT_6") (pintype "passive"))
    )
    (net (code "98") (name "/VDDA") (class "Default")
      (node (ref "C11") (pin "2") (pinfunction "2_2") (pintype "passive"))
      (node (ref "C12") (pin "2") (pinfunction "2_2") (pintype "passive"))
      (node (ref "R3") (pin "1") (pinfunction "1_1") (pintype "passive"))
      (node (ref "U1") (pin "32") (pinfunction "Vref+_32") (pintype "passive"))
      (node (ref "U1") (pin "33") (pinfunction "VDDA_33") (pintype "passive"))
    )
    (net (code "99") (name "/WiFi_ANT") (class "Default")
      (node (ref "C13") (pin "2") (pinfunction "2_2") (pintype "passive"))
      (node (ref "C22") (pin "2") (pinfunction "2_2") (pintype "passive"))
      (node (ref "U7") (pin "17") (pinfunction "ANT_2.4G_17") (pintype "passive"))
    )
    (net (code "100") (name "/WiFi_Linked") (class "Default")
      (node (ref "LED2") (pin "2") (pinfunction "2_2") (pintype "passive"))
      (node (ref "R13") (pin "1") (pinfunction "1_1") (pintype "passive"))
      (node (ref "U7") (pin "13") (pinfunction "nLink_13") (pintype "passive"))
    )
    (net (code "101") (name "/WiFi_Reload") (class "Default")
      (node (ref "K1") (pin "2") (pinfunction "2_2") (pintype "passive"))
      (node (ref "R14") (pin "1") (pinfunction "1_1") (pintype "passive"))
      (node (ref "U7") (pin "12") (pinfunction "nReload_12") (pintype "passive"))
    )
    (net (code "102") (name "/WiFi_Reload(C10)") (class "Default")
      (node (ref "U1") (pin "111") (pinfunction "PC10/SPI3_SCK/U3_TX/U4_TX/SDIO_D2/DCMI_D8/I2S3_CK_111") (pintype "passive"))
    )
    (net (code "103") (name "/WiFi_Reload(E15)") (class "Default")
      (node (ref "R14") (pin "2") (pinfunction "2_2") (pintype "passive"))
      (node (ref "U1") (pin "68") (pinfunction "PE15/FSMC_D12/TIM1_BKIN_68") (pintype "passive"))
    )
    (net (code "104") (name "/Wifi_Connect(D11)") (class "Default")
      (node (ref "R13") (pin "2") (pinfunction "2_2") (pintype "passive"))
      (node (ref "U1") (pin "80") (pinfunction "PD11/FSMC_A16/FSMC_CLE/U3_CTS_80") (pintype "passive"))
    )
    (net (code "105") (name "3.3V") (class "Default")
      (node (ref "B1") (pin "1") (pinfunction "P_1") (pintype "passive"))
      (node (ref "C14") (pin "2") (pinfunction "2_2") (pintype "passive"))
      (node (ref "C15") (pin "2") (pinfunction "2_2") (pintype "passive"))
      (node (ref "C16") (pin "2") (pinfunction "2_2") (pintype "passive"))
      (node (ref "C17") (pin "2") (pinfunction "2_2") (pintype "passive"))
      (node (ref "C18") (pin "2") (pinfunction "2_2") (pintype "passive"))
      (node (ref "C19") (pin "2") (pinfunction "2_2") (pintype "passive"))
      (node (ref "C20") (pin "2") (pinfunction "2_2") (pintype "passive"))
      (node (ref "C21") (pin "2") (pinfunction "2_2") (pintype "passive"))
      (node (ref "C26") (pin "1") (pinfunction "1_1") (pintype "passive"))
      (node (ref "C3") (pin "1") (pinfunction "1_1") (pintype "passive"))
      (node (ref "C4") (pin "2") (pinfunction "2_2") (pintype "passive"))
      (node (ref "C8") (pin "1") (pinfunction "1_1") (pintype "passive"))
      (node (ref "D1") (pin "2") (pinfunction "2_2") (pintype "passive"))
      (node (ref "LED1") (pin "1") (pintype "passive"))
      (node (ref "P1") (pin "1") (pinfunction "1_1") (pintype "passive"))
      (node (ref "P3") (pin "2") (pinfunction "2_2") (pintype "passive"))
      (node (ref "P4") (pin "18") (pinfunction "18_18") (pintype "passive"))
      (node (ref "P6") (pin "11") (pinfunction "11_11") (pintype "passive"))
      (node (ref "P9") (pin "1") (pinfunction "1_1") (pintype "passive"))
      (node (ref "R11") (pin "2") (pinfunction "2_2") (pintype "passive"))
      (node (ref "R12") (pin "1") (pinfunction "1_1") (pintype "passive"))
      (node (ref "R15") (pin "1") (pinfunction "1_1") (pintype "passive"))
      (node (ref "R16") (pin "1") (pinfunction "1_1") (pintype "passive"))
      (node (ref "R2") (pin "2") (pinfunction "2_2") (pintype "passive"))
      (node (ref "R2") (pin "4") (pinfunction "4_4") (pintype "passive"))
      (node (ref "R3") (pin "2") (pinfunction "2_2") (pintype "passive"))
      (node (ref "R4") (pin "2") (pinfunction "2_2") (pintype "passive"))
      (node (ref "R5") (pin "1") (pinfunction "1_1") (pintype "passive"))
      (node (ref "R7") (pin "2") (pinfunction "2_2") (pintype "passive"))
      (node (ref "U1") (pin "108") (pinfunction "VDD_108") (pintype "passive"))
      (node (ref "U1") (pin "121") (pinfunction "VDD_121") (pintype "passive"))
      (node (ref "U1") (pin "131") (pinfunction "VDD_131") (pintype "passive"))
      (node (ref "U1") (pin "144") (pinfunction "VDD_144") (pintype "passive"))
      (node (ref "U1") (pin "17") (pinfunction "VDD_17") (pintype "passive"))
      (node (ref "U1") (pin "30") (pinfunction "VDD_30") (pintype "passive"))
      (node (ref "U1") (pin "39") (pinfunction "VDD_39") (pintype "passive"))
      (node (ref "U1") (pin "52") (pinfunction "VDD_52") (pintype "passive"))
      (node (ref "U1") (pin "62") (pinfunction "VDD_62") (pintype "passive"))
      (node (ref "U1") (pin "72") (pinfunction "VDD_72") (pintype "passive"))
      (node (ref "U1") (pin "84") (pinfunction "VDD_84") (pintype "passive"))
      (node (ref "U1") (pin "95") (pinfunction "VDD_95") (pintype "passive"))
      (node (ref "U2") (pin "2") (pinfunction "OUT_2") (pintype "passive"))
      (node (ref "U2") (pin "4") (pinfunction "OUT_4") (pintype "passive"))
      (node (ref "U5") (pin "11") (pinfunction "VCC_11") (pintype "passive"))
      (node (ref "U5") (pin "2") (pinfunction "VCC_2") (pintype "passive"))
      (node (ref "U6") (pin "3") (pinfunction "~{WP}_3") (pintype "passive"))
      (node (ref "U6") (pin "7") (pinfunction "~{RESET}_7") (pintype "passive"))
      (node (ref "U6") (pin "8") (pinfunction "VCC_8") (pintype "passive"))
      (node (ref "U7") (pin "15") (pinfunction "DVDD_15") (pintype "passive"))
      (node (ref "U8") (pin "2") (pinfunction "2_2") (pintype "passive"))
    )
    (net (code "106") (name "5.0V") (class "Default")
      (node (ref "C1") (pin "1") (pinfunction "1_1") (pintype "passive"))
      (node (ref "C2") (pin "2") (pinfunction "2_2") (pintype "passive"))
      (node (ref "C5") (pin "1") (pinfunction "1_1") (pintype "passive"))
      (node (ref "C6") (pin "1") (pinfunction "1_1") (pintype "passive"))
      (node (ref "F1") (pin "2") (pinfunction "2_2") (pintype "passive"))
      (node (ref "P7") (pin "1") (pinfunction "1_1") (pintype "passive"))
      (node (ref "R2") (pin "6") (pinfunction "6_6") (pintype "passive"))
      (node (ref "U2") (pin "3") (pinfunction "IN_3") (pintype "passive"))
      (node (ref "U3") (pin "7") (pinfunction "REG_7") (pintype "passive"))
      (node (ref "U3") (pin "8") (pinfunction "VBUS_8") (pintype "passive"))
    )
    (net (code "107") (name "GND") (class "Default")
      (node (ref "C1") (pin "2") (pinfunction "2_2") (pintype "passive"))
      (node (ref "C10") (pin "1") (pinfunction "1_1") (pintype "passive"))
      (node (ref "C11") (pin "1") (pinfunction "1_1") (pintype "passive"))
      (node (ref "C12") (pin "1") (pinfunction "1_1") (pintype "passive"))
      (node (ref "C14") (pin "1") (pinfunction "1_1") (pintype "passive"))
      (node (ref "C15") (pin "1") (pinfunction "1_1") (pintype "passive"))
      (node (ref "C16") (pin "1") (pinfunction "1_1") (pintype "passive"))
      (node (ref "C17") (pin "1") (pinfunction "1_1") (pintype "passive"))
      (node (ref "C18") (pin "1") (pinfunction "1_1") (pintype "passive"))
      (node (ref "C19") (pin "1") (pinfunction "1_1") (pintype "passive"))
      (node (ref "C2") (pin "1") (pinfunction "1_1") (pintype "passive"))
      (node (ref "C20") (pin "1") (pinfunction "1_1") (pintype "passive"))
      (node (ref "C21") (pin "1") (pinfunction "1_1") (pintype "passive"))
      (node (ref "C22") (pin "1") (pinfunction "1_1") (pintype "passive"))
      (node (ref "C23") (pin "1") (pinfunction "1_1") (pintype "passive"))
      (node (ref "C24") (pin "2") (pinfunction "2_2") (pintype "passive"))
      (node (ref "C25") (pin "2") (pinfunction "2_2") (pintype "passive"))
      (node (ref "C26") (pin "2") (pinfunction "2_2") (pintype "passive"))
      (node (ref "C3") (pin "2") (pinfunction "2_2") (pintype "passive"))
      (node (ref "C4") (pin "1") (pinfunction "1_1") (pintype "passive"))
      (node (ref "C5") (pin "2") (pinfunction "2_2") (pintype "passive"))
      (node (ref "C6") (pin "2") (pinfunction "2_2") (pintype "passive"))
      (node (ref "C7") (pin "2") (pinfunction "2_2") (pintype "passive"))
      (node (ref "C8") (pin "2") (pinfunction "2_2") (pintype "passive"))
      (node (ref "C9") (pin "1") (pinfunction "1_1") (pintype "passive"))
      (node (ref "D1") (pin "1") (pintype "passive"))
      (node (ref "J1") (pin "2") (pinfunction "GND_2") (pintype "passive"))
      (node (ref "J1") (pin "3") (pinfunction "GND_3") (pintype "passive"))
      (node (ref "K1") (pin "1") (pinfunction "1_1") (pintype "passive"))
      (node (ref "K2") (pin "2") (pinfunction "2_2") (pintype "passive"))
      (node (ref "K3") (pin "2") (pinfunction "2_2") (pintype "passive"))
      (node (ref "P1") (pin "4") (pinfunction "4_4") (pintype "passive"))
      (node (ref "P2") (pin "5") (pinfunction "B4_5") (pintype "passive"))
      (node (ref "P2") (pin "6") (pinfunction "B3_6") (pintype "passive"))
      (node (ref "P2") (pin "7") (pinfunction "B2_7") (pintype "passive"))
      (node (ref "P2") (pin "8") (pinfunction "B1_8") (pintype "passive"))
      (node (ref "P3") (pin "1") (pinfunction "1_1") (pintype "passive"))
      (node (ref "P3") (pin "7") (pinfunction "7_7") (pintype "passive"))
      (node (ref "P4") (pin "2") (pinfunction "2_2") (pintype "passive"))
      (node (ref "P4") (pin "3") (pinfunction "3_3") (pintype "passive"))
      (node (ref "P6") (pin "10") (pinfunction "10_10") (pintype "passive"))
      (node (ref "P6") (pin "20") (pinfunction "20_20") (pintype "passive"))
      (node (ref "P7") (pin "2") (pinfunction "2_2") (pintype "passive"))
      (node (ref "P9") (pin "2") (pinfunction "2_2") (pintype "passive"))
      (node (ref "Q1") (pin "2") (pinfunction "E_2") (pintype "passive"))
      (node (ref "R1") (pin "1") (pinfunction "1_1") (pintype "passive"))
      (node (ref "R10") (pin "2") (pinfunction "2_2") (pintype "passive"))
      (node (ref "R2") (pin "8") (pinfunction "8_8") (pintype "passive"))
      (node (ref "R6") (pin "2") (pinfunction "2_2") (pintype "passive"))
      (node (ref "U1") (pin "107") (pinfunction "VSS_107") (pintype "passive"))
      (node (ref "U1") (pin "120") (pinfunction "VSS_120") (pintype "passive"))
      (node (ref "U1") (pin "130") (pinfunction "VSS_130") (pintype "passive"))
      (node (ref "U1") (pin "16") (pinfunction "VSS_16") (pintype "passive"))
      (node (ref "U1") (pin "31") (pinfunction "VSSA_31") (pintype "passive"))
      (node (ref "U1") (pin "38") (pinfunction "VSS_38") (pintype "passive"))
      (node (ref "U1") (pin "51") (pinfunction "VSS_51") (pintype "passive"))
      (node (ref "U1") (pin "61") (pinfunction "VSS_61") (pintype "passive"))
      (node (ref "U1") (pin "83") (pinfunction "VSS_83") (pintype "passive"))
      (node (ref "U1") (pin "94") (pinfunction "VSS_94") (pintype "passive"))
      (node (ref "U2") (pin "1") (pinfunction "GND_1") (pintype "passive"))
      (node (ref "U3") (pin "3") (pinfunction "GND_3") (pintype "passive"))
      (node (ref "U4") (pin "5") (pinfunction "GND_5") (pintype "power_in"))
      (node (ref "U5") (pin "5") (pinfunction "GND_5") (pintype "passive"))
      (node (ref "U5") (pin "8") (pinfunction "GND_8") (pintype "passive"))
      (node (ref "U6") (pin "4") (pinfunction "GND_4") (pintype "passive"))
      (node (ref "U7") (pin "16") (pinfunction "GND_16") (pintype "passive"))
      (node (ref "X1") (pin "3") (pinfunction "3_3") (pintype "passive"))
    )
    (net (code "108") (name "Net-(B1-G)") (class "Default")
      (node (ref "B1") (pin "2") (pinfunction "G_2") (pintype "passive"))
      (node (ref "Q1") (pin "3") (pinfunction "C_3") (pintype "passive"))
    )
    (net (code "109") (name "Net-(J1-ANT)") (class "Default")
      (node (ref "C13") (pin "1") (pinfunction "1_1") (pintype "passive"))
      (node (ref "C23") (pin "2") (pinfunction "2_2") (pintype "passive"))
      (node (ref "J1") (pin "1") (pinfunction "ANT_1") (pintype "passive"))
    )
    (net (code "110") (name "Net-(LED1-Pad2)") (class "Default")
      (node (ref "LED1") (pin "2") (pinfunction "2_2") (pintype "passive"))
      (node (ref "R1") (pin "2") (pinfunction "2_2") (pintype "passive"))
    )
    (net (code "111") (name "Net-(LED2-Pad1)") (class "Default")
      (node (ref "LED2") (pin "1") (pintype "passive"))
      (node (ref "R5") (pin "2") (pinfunction "2_2") (pintype "passive"))
    )
    (net (code "112") (name "Net-(Q1-B)") (class "Default")
      (node (ref "Q1") (pin "1") (pinfunction "B_1") (pintype "passive"))
      (node (ref "R8") (pin "7") (pinfunction "7_7") (pintype "passive"))
    )
    (net (code "113") (name "Net-(U1-PDR_ON)") (class "Default")
      (node (ref "R4") (pin "1") (pinfunction "1_1") (pintype "passive"))
      (node (ref "U1") (pin "143") (pinfunction "PDR_ON_143") (pintype "passive"))
    )
    (net (code "114") (name "Net-(U1-Vcap_1)") (class "Default")
      (node (ref "C9") (pin "2") (pinfunction "2_2") (pintype "passive"))
      (node (ref "U1") (pin "71") (pinfunction "Vcap_1_71") (pintype "passive"))
    )
    (net (code "115") (name "Net-(U1-Vcap_2)") (class "Default")
      (node (ref "C10") (pin "2") (pinfunction "2_2") (pintype "passive"))
      (node (ref "U1") (pin "106") (pinfunction "Vcap_2_106") (pintype "passive"))
    )
    (net (code "116") (name "Net-(U3-VDD)") (class "Default")
      (node (ref "C7") (pin "1") (pinfunction "1_1") (pintype "passive"))
      (node (ref "U3") (pin "6") (pinfunction "VDD_6") (pintype "passive"))
    )
    (net (code "117") (name "Net-(U8-B)") (class "Default")
      (node (ref "R8") (pin "1") (pinfunction "1_1") (pintype "passive"))
      (node (ref "U8") (pin "1") (pinfunction "B_1") (pintype "passive"))
    )
    (net (code "118") (name "Net-(U8-G)") (class "Default")
      (node (ref "R8") (pin "3") (pinfunction "3_3") (pintype "passive"))
      (node (ref "U8") (pin "3") (pinfunction "G_3") (pintype "passive"))
    )
    (net (code "119") (name "Net-(U8-R)") (class "Default")
      (node (ref "R8") (pin "5") (pinfunction "5_5") (pintype "passive"))
      (node (ref "U8") (pin "4") (pinfunction "R_4") (pintype "passive"))
    )
    (net (code "120") (name "POWER_5V_IN") (class "Default")
      (node (ref "F1") (pin "1") (pinfunction "1_1") (pintype "passive"))
      (node (ref "P4") (pin "19") (pinfunction "19_19") (pintype "passive"))
      (node (ref "U4") (pin "1") (pinfunction "VCC_1") (pintype "power_in"))
    )
    (net (code "121") (name "unconnected-(U1-PA12{slash}TIM1_ETR{slash}U1_RTS{slash}CAN1_TX{slash}OTG_FS_DP-Pad104)") (class "Default")
      (node (ref "U1") (pin "104") (pinfunction "PA12/TIM1_ETR/U1_RTS/CAN1_TX/OTG_FS_DP_104") (pintype "passive"))
    )
    (net (code "122") (name "unconnected-(U1-PC13{slash}RTC_AF1-Pad7)") (class "Default")
      (node (ref "U1") (pin "7") (pinfunction "PC13/RTC_AF1_7") (pintype "passive+no_connect"))
    )
    (net (code "123") (name "unconnected-(U1-PC14-OSC32_IN-Pad8)") (class "Default")
      (node (ref "U1") (pin "8") (pinfunction "PC14-OSC32_IN_8") (pintype "passive+no_connect"))
    )
    (net (code "124") (name "unconnected-(U1-PC15-OSC32_OUT-Pad9)") (class "Default")
      (node (ref "U1") (pin "9") (pinfunction "PC15-OSC32_OUT_9") (pintype "passive+no_connect"))
    )
    (net (code "125") (name "unconnected-(U1-PD5{slash}FSMC_NWE{slash}U2_TX-Pad119)") (class "Default")
      (node (ref "U1") (pin "119") (pinfunction "PD5/FSMC_NWE/U2_TX_119") (pintype "passive+no_connect"))
    )
    (net (code "126") (name "unconnected-(U1-PE4{slash}TRACED1{slash}FSMC_A20{slash}DCMI_D4-Pad3)") (class "Default")
      (node (ref "U1") (pin "3") (pinfunction "PE4/TRACED1/FSMC_A20/DCMI_D4_3") (pintype "passive"))
    )
    (net (code "127") (name "unconnected-(U1-PE7{slash}FSMC_D4{slash}TIM1_ETR-Pad58)") (class "Default")
      (node (ref "U1") (pin "58") (pinfunction "PE7/FSMC_D4/TIM1_ETR_58") (pintype "passive"))
    )
    (net (code "128") (name "unconnected-(U1-PF2{slash}FSMC_A2{slash}I2C2_SMBA-Pad12)") (class "Default")
      (node (ref "U1") (pin "12") (pinfunction "PF2/FSMC_A2/I2C2_SMBA_12") (pintype "passive"))
    )
    (net (code "129") (name "unconnected-(U1-PF10{slash}FSMC_INTR{slash}ADC3_IN8-Pad22)") (class "Default")
      (node (ref "U1") (pin "22") (pinfunction "PF10/FSMC_INTR/ADC3_IN8_22") (pintype "passive"))
    )
    (net (code "130") (name "unconnected-(U1-PF11{slash}DCMI_D12-Pad49)") (class "Default")
      (node (ref "U1") (pin "49") (pinfunction "PF11/DCMI_D12_49") (pintype "passive"))
    )
    (net (code "131") (name "unconnected-(U1-PF12{slash}FSMC_A6-Pad50)") (class "Default")
      (node (ref "U1") (pin "50") (pinfunction "PF12/FSMC_A6_50") (pintype "passive"))
    )
    (net (code "132") (name "unconnected-(U1-PF13{slash}FSMC_A7-Pad53)") (class "Default")
      (node (ref "U1") (pin "53") (pinfunction "PF13/FSMC_A7_53") (pintype "passive"))
    )
    (net (code "133") (name "unconnected-(U1-PF14{slash}FSMC_A8-Pad54)") (class "Default")
      (node (ref "U1") (pin "54") (pinfunction "PF14/FSMC_A8_54") (pintype "passive"))
    )
    (net (code "134") (name "unconnected-(U1-PF15{slash}FSMC_A9-Pad55)") (class "Default")
      (node (ref "U1") (pin "55") (pinfunction "PF15/FSMC_A9_55") (pintype "passive"))
    )
    (net (code "135") (name "unconnected-(U1-PG0{slash}FSMC_A10-Pad56)") (class "Default")
      (node (ref "U1") (pin "56") (pinfunction "PG0/FSMC_A10_56") (pintype "passive"))
    )
    (net (code "136") (name "unconnected-(U1-PG1{slash}FSMC_A11-Pad57)") (class "Default")
      (node (ref "U1") (pin "57") (pinfunction "PG1/FSMC_A11_57") (pintype "passive"))
    )
    (net (code "137") (name "unconnected-(U1-PG2{slash}FSMC_A12-Pad87)") (class "Default")
      (node (ref "U1") (pin "87") (pinfunction "PG2/FSMC_A12_87") (pintype "passive"))
    )
    (net (code "138") (name "unconnected-(U1-PG4{slash}FSMC_A14-Pad89)") (class "Default")
      (node (ref "U1") (pin "89") (pinfunction "PG4/FSMC_A14_89") (pintype "passive"))
    )
    (net (code "139") (name "unconnected-(U1-PG5{slash}FSMC_A15-Pad90)") (class "Default")
      (node (ref "U1") (pin "90") (pinfunction "PG5/FSMC_A15_90") (pintype "passive"))
    )
    (net (code "140") (name "unconnected-(U1-PG6{slash}FSMC_INT2-Pad91)") (class "Default")
      (node (ref "U1") (pin "91") (pinfunction "PG6/FSMC_INT2_91") (pintype "passive"))
    )
    (net (code "141") (name "unconnected-(U1-PG7{slash}FSMC_INT3{slash}U6_CK-Pad92)") (class "Default")
      (node (ref "U1") (pin "92") (pinfunction "PG7/FSMC_INT3/U6_CK_92") (pintype "passive"))
    )
    (net (code "142") (name "unconnected-(U1-PG8{slash}U6_RTS{slash}ETH_PPS_OUT-Pad93)") (class "Default")
      (node (ref "U1") (pin "93") (pinfunction "PG8/U6_RTS/ETH_PPS_OUT_93") (pintype "passive"))
    )
    (net (code "143") (name "unconnected-(U1-PG15{slash}U6_CTS{slash}DCMI_D13-Pad132)") (class "Default")
      (node (ref "U1") (pin "132") (pinfunction "PG15/U6_CTS/DCMI_D13_132") (pintype "passive"))
    )
    (net (code "144") (name "unconnected-(U3-CTS-Pad23)") (class "Default")
      (node (ref "U3") (pin "23") (pinfunction "CTS_23") (pintype "passive+no_connect"))
    )
    (net (code "145") (name "unconnected-(U3-DCO-Pad1)") (class "Default")
      (node (ref "U3") (pin "1") (pinfunction "DCO_1") (pintype "passive+no_connect"))
    )
    (net (code "146") (name "unconnected-(U3-DSR-Pad27)") (class "Default")
      (node (ref "U3") (pin "27") (pinfunction "DSR_27") (pintype "passive+no_connect"))
    )
    (net (code "147") (name "unconnected-(U3-DTR-Pad28)") (class "Default")
      (node (ref "U3") (pin "28") (pinfunction "DTR_28") (pintype "passive+no_connect"))
    )
    (net (code "148") (name "unconnected-(U3-NC-Pad10)") (class "Default")
      (node (ref "U3") (pin "10") (pinfunction "NC_10") (pintype "passive+no_connect"))
    )
    (net (code "149") (name "unconnected-(U3-NC-Pad13)") (class "Default")
      (node (ref "U3") (pin "13") (pinfunction "NC_13") (pintype "passive+no_connect"))
    )
    (net (code "150") (name "unconnected-(U3-NC-Pad14)") (class "Default")
      (node (ref "U3") (pin "14") (pinfunction "NC_14") (pintype "passive+no_connect"))
    )
    (net (code "151") (name "unconnected-(U3-NC-Pad15)") (class "Default")
      (node (ref "U3") (pin "15") (pinfunction "NC_15") (pintype "passive+no_connect"))
    )
    (net (code "152") (name "unconnected-(U3-NC-Pad16)") (class "Default")
      (node (ref "U3") (pin "16") (pinfunction "NC_16") (pintype "passive+no_connect"))
    )
    (net (code "153") (name "unconnected-(U3-NC-Pad17)") (class "Default")
      (node (ref "U3") (pin "17") (pinfunction "NC_17") (pintype "passive+no_connect"))
    )
    (net (code "154") (name "unconnected-(U3-NC-Pad19)") (class "Default")
      (node (ref "U3") (pin "19") (pinfunction "NC_19") (pintype "passive+no_connect"))
    )
    (net (code "155") (name "unconnected-(U3-NC-Pad20)") (class "Default")
      (node (ref "U3") (pin "20") (pinfunction "NC_20") (pintype "passive+no_connect"))
    )
    (net (code "156") (name "unconnected-(U3-NC-Pad21)") (class "Default")
      (node (ref "U3") (pin "21") (pinfunction "NC_21") (pintype "passive+no_connect"))
    )
    (net (code "157") (name "unconnected-(U3-NC-Pad22)") (class "Default")
      (node (ref "U3") (pin "22") (pinfunction "NC_22") (pintype "passive+no_connect"))
    )
    (net (code "158") (name "unconnected-(U3-RI-Pad2)") (class "Default")
      (node (ref "U3") (pin "2") (pinfunction "RI_2") (pintype "passive+no_connect"))
    )
    (net (code "159") (name "unconnected-(U3-RTS-Pad24)") (class "Default")
      (node (ref "U3") (pin "24") (pinfunction "RTS_24") (pintype "passive+no_connect"))
    )
    (net (code "160") (name "unconnected-(U3-SUS-Pad12)") (class "Default")
      (node (ref "U3") (pin "12") (pinfunction "SUS_12") (pintype "passive+no_connect"))
    )
    (net (code "161") (name "unconnected-(U3-VPP-Pad18)") (class "Default")
      (node (ref "U3") (pin "18") (pinfunction "VPP_18") (pintype "passive+no_connect"))
    )
    (net (code "162") (name "unconnected-(U4-ID-Pad4)") (class "Default")
      (node (ref "U4") (pin "4") (pinfunction "ID_4") (pintype "power_in"))
    )
    (net (code "163") (name "unconnected-(U5-D0-Pad1)") (class "Default")
      (node (ref "U5") (pin "1") (pinfunction "D0_1") (pintype "passive"))
    )
    (net (code "164") (name "unconnected-(U5-D1-Pad6)") (class "Default")
      (node (ref "U5") (pin "6") (pinfunction "D1_6") (pintype "passive"))
    )
    (net (code "165") (name "unconnected-(U5-D2-Pad12)") (class "Default")
      (node (ref "U5") (pin "12") (pinfunction "D2_12") (pintype "passive"))
    )
    (net (code "166") (name "unconnected-(U5-D3-Pad7)") (class "Default")
      (node (ref "U5") (pin "7") (pinfunction "D3_7") (pintype "passive"))
    )
    (net (code "167") (name "unconnected-(U7-GPIO1-Pad1)") (class "Default")
      (node (ref "U7") (pin "1") (pinfunction "GPIO1_1") (pintype "passive"))
    )
    (net (code "168") (name "unconnected-(U7-GPIO2-Pad2)") (class "Default")
      (node (ref "U7") (pin "2") (pinfunction "GPIO2_2") (pintype "passive"))
    )
    (net (code "169") (name "unconnected-(U7-GPIO3-Pad3)") (class "Default")
      (node (ref "U7") (pin "3") (pinfunction "GPIO3_3") (pintype "passive"))
    )
    (net (code "170") (name "unconnected-(U7-GPIO4-Pad4)") (class "Default")
      (node (ref "U7") (pin "4") (pinfunction "GPIO4_4") (pintype "passive"))
    )
    (net (code "171") (name "unconnected-(U7-UART0_CTS-Pad7)") (class "Default")
      (node (ref "U7") (pin "7") (pinfunction "UART0_CTS_7") (pintype "passive"))
    )
    (net (code "172") (name "unconnected-(U7-UART0_RTS-Pad8)") (class "Default")
      (node (ref "U7") (pin "8") (pinfunction "UART0_RTS_8") (pintype "passive"))
    )
    (net (code "173") (name "unconnected-(U7-WPS-Pad9)") (class "Default")
      (node (ref "U7") (pin "9") (pinfunction "WPS_9") (pintype "passive"))
    )
    (net (code "174") (name "unconnected-(U7-WPS-Pad14)") (class "Default")
      (node (ref "U7") (pin "14") (pinfunction "WPS_14") (pintype "passive"))
    )
    (net (code "175") (name "unconnected-(U7-nReady-Pad11)") (class "Default")
      (node (ref "U7") (pin "11") (pinfunction "nReady_11") (pintype "passive"))
    )
    (net (code "176") (name "unconnected-(U7-nReset-Pad10)") (class "Default")
      (node (ref "U7") (pin "10") (pinfunction "nReset_10") (pintype "passive"))
    )
  )
)
